# MCU.net
KiCad netlist of a schematic drawn in Altium Designer
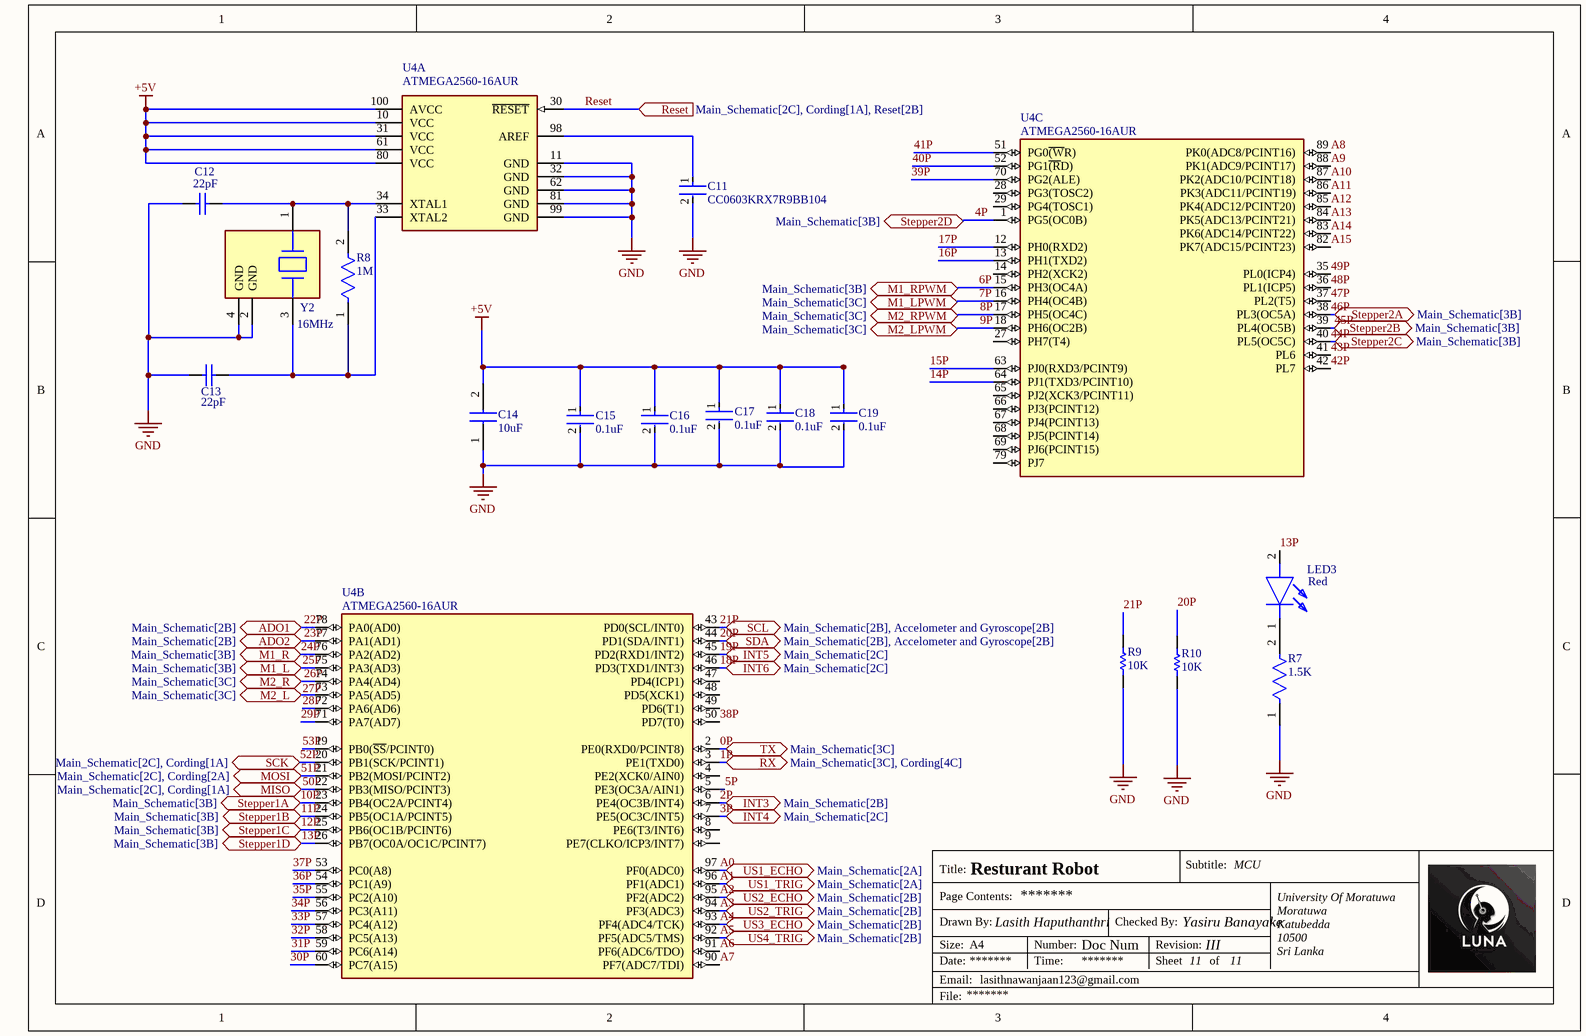
[diagram p0: MCU.SchDoc]

(export (version "E")
  (design (tool "Eeschema 10.0.6"))
  (components
    (comp (ref "C11")
      (value "CC0603KRX7R9BB104")
      (footprint "FP-CC0603-DA-MFG")
      (description "CAP CER 0.1UF 50V X7R 0603")
      (fields (field (name "MANUFACTURER") "YAGEO") (field (name "VOLTAGE") "50 V"))
      (libsource (lib "Altium Content Vault") (part "11868f565c42a9108669ba33697ecf6"))
    )
    (comp (ref "C12")
      (value "22pF")
      (footprint "CAPC1608X90X40LL10T20")
      (libsource (lib "Altium Content Vault") (part "CAP-NP-2"))
    )
    (comp (ref "C13")
      (value "22pF")
      (footprint "CAPC1608X90X40LL10T20")
      (libsource (lib "Altium Content Vault") (part "CAP-NP-2"))
    )
    (comp (ref "C14")
      (value "10uF")
      (footprint "SamacSys:CAPC1608X90N")
      (description "CL10A106KP8NNNC Capacitor")
      (fields
        (field (name "MANUFACTURER_PART_NUMBER") "CL10A106KP8NNNC")
        (field (name "MOUSER PART NUMBER") "187-CL10A106KP8NNNC")
      )
      (libsource (lib "*") (part "CL10A106KP8NNNC"))
    )
    (comp (ref "C15")
      (value "0.1uF")
      (footprint "FP-CC0603-DA-MFG")
      (description "CC0603KRX7R9BB104 CAP CER 0.1UF 50V X7R 0603")
      (fields (field (name "MANUFACTURER") "YAGEO") (field (name "VOLTAGE") "50 V"))
      (libsource (lib "Altium Content Vault") (part "11868f565c42a9108669ba33697ecf6"))
    )
    (comp (ref "C16")
      (value "0.1uF")
      (footprint "FP-CC0603-DA-MFG")
      (description "CC0603KRX7R9BB104 CAP CER 0.1UF 50V X7R 0603")
      (fields (field (name "MANUFACTURER") "YAGEO") (field (name "VOLTAGE") "50 V"))
      (libsource (lib "Altium Content Vault") (part "11868f565c42a9108669ba33697ecf6"))
    )
    (comp (ref "C17")
      (value "0.1uF")
      (footprint "FP-CC0603-DA-MFG")
      (description "CC0603KRX7R9BB104 CAP CER 0.1UF 50V X7R 0603")
      (fields (field (name "MANUFACTURER") "YAGEO") (field (name "VOLTAGE") "50 V"))
      (libsource (lib "Altium Content Vault") (part "11868f565c42a9108669ba33697ecf6"))
    )
    (comp (ref "C18")
      (value "0.1uF")
      (footprint "FP-CC0603-DA-MFG")
      (description "CC0603KRX7R9BB104 CAP CER 0.1UF 50V X7R 0603")
      (fields (field (name "MANUFACTURER") "YAGEO") (field (name "VOLTAGE") "50 V"))
      (libsource (lib "Altium Content Vault") (part "11868f565c42a9108669ba33697ecf6"))
    )
    (comp (ref "C19")
      (value "0.1uF")
      (footprint "FP-CC0603-DA-MFG")
      (description "CC0603KRX7R9BB104 CAP CER 0.1UF 50V X7R 0603")
      (fields (field (name "MANUFACTURER") "YAGEO") (field (name "VOLTAGE") "50 V"))
      (libsource (lib "Altium Content Vault") (part "11868f565c42a9108669ba33697ecf6"))
    )
    (comp (ref "LED3")
      (value "Red")
      (footprint "SamacSys:LEDC1608X55N")
      (description "LED")
      (fields
        (field (name "MANUFACTURER_PART_NUMBER") "LTST-C191KRKT")
        (field (name "MOUSER PART NUMBER") "859-LTST-C191KRKT")
      )
      (libsource (lib "*") (part "LTST-C191KRKT"))
    )
    (comp (ref "R7")
      (value "1.5K")
      (footprint "FP-AF0603-IPC_B")
      (description "AF0603FR-071K5L Anti-Sulfurated Chip Resistors Automotive Grade 1.5kΩ 1% 100ppm/°C 0603")
      (fields (field (name "TOLERANCE") "1%"))
      (libsource (lib "Altium Content Vault") (part "1029c3af85768c4190bb7ad29bc67b5"))
    )
    (comp (ref "R8")
      (value "1M")
      (footprint "FP-AF0603-IPC_B")
      (description "AF0603FR-071K5L Anti-Sulfurated Chip Resistors Automotive Grade 1.5kΩ 1% 100ppm/°C 0603")
      (fields (field (name "TOLERANCE") "1%"))
      (libsource (lib "Altium Content Vault") (part "1029c3af85768c4190bb7ad29bc67b5"))
    )
    (comp (ref "R9")
      (value "10K")
      (footprint "RESC1608X55X25ML10T15")
      (fields (field (name "MANUFACTURER") "Yageo") (field (name "TOLERANCE") "5%"))
      (libsource (lib "Altium Content Vault") (part "RES-2"))
    )
    (comp (ref "R10")
      (value "10K")
      (footprint "RESC1608X55X25ML10T15")
      (fields (field (name "MANUFACTURER") "Yageo") (field (name "TOLERANCE") "5%"))
      (libsource (lib "Altium Content Vault") (part "RES-2"))
    )
    (comp (ref "U4")
      (value "ATMEGA2560-16AUR")
      (footprint "FP-100A-MFG")
      (description "IC MCU 8BIT 256KB FLASH 100TQFP")
      (libsource (lib "Altium Content Vault") (part "7a986b9e50de34ed0d2049ae6a26084"))
    )
    (comp (ref "Y2")
      (value "16MHz")
      (footprint "FP-ABM8G-MFG")
      (fields (field (name "TOLERANCE") "20ppm"))
      (libsource (lib "Altium Content Vault") (part "48e526d86b7f2615d98721063c72f49"))
    )
  )
  (nets
    (net (code "1") (name "+5V") (class "Default")
      (node (ref "C14") (pin "2") (pinfunction "2_2") (pintype "passive"))
      (node (ref "C15") (pin "1") (pinfunction "1_1") (pintype "passive"))
      (node (ref "C16") (pin "1") (pinfunction "1_1") (pintype "passive"))
      (node (ref "C17") (pin "1") (pinfunction "1_1") (pintype "passive"))
      (node (ref "C18") (pin "1") (pinfunction "1_1") (pintype "passive"))
      (node (ref "C19") (pin "1") (pinfunction "1_1") (pintype "passive"))
      (node (ref "U4") (pin "10") (pinfunction "VCC_10") (pintype "power_in"))
      (node (ref "U4") (pin "100") (pinfunction "AVCC_100") (pintype "power_in"))
      (node (ref "U4") (pin "31") (pinfunction "VCC_31") (pintype "power_in"))
      (node (ref "U4") (pin "61") (pinfunction "VCC_61") (pintype "power_in"))
      (node (ref "U4") (pin "80") (pinfunction "VCC_80") (pintype "power_in"))
    )
    (net (code "2") (name "/0P") (class "Default")
      (node (ref "U4") (pin "2") (pinfunction "PE0(RXD0/PCINT8)_2") (pintype "bidirectional"))
    )
    (net (code "3") (name "/1P") (class "Default")
      (node (ref "U4") (pin "3") (pinfunction "PE1(TXD0)_3") (pintype "bidirectional"))
    )
    (net (code "4") (name "/2P") (class "Default")
      (node (ref "U4") (pin "6") (pinfunction "PE4(OC3B/INT4)_6") (pintype "bidirectional"))
    )
    (net (code "5") (name "/3P") (class "Default")
      (node (ref "U4") (pin "7") (pinfunction "PE5(OC3C/INT5)_7") (pintype "bidirectional"))
    )
    (net (code "6") (name "/4P") (class "Default")
      (node (ref "U4") (pin "1") (pinfunction "PG5(OC0B)_1") (pintype "bidirectional"))
    )
    (net (code "7") (name "/5P") (class "Default")
      (node (ref "U4") (pin "5") (pinfunction "PE3(OC3A/AIN1)_5") (pintype "bidirectional"))
    )
    (net (code "8") (name "/6P") (class "Default")
      (node (ref "U4") (pin "15") (pinfunction "PH3(OC4A)_15") (pintype "bidirectional"))
    )
    (net (code "9") (name "/7P") (class "Default")
      (node (ref "U4") (pin "16") (pinfunction "PH4(OC4B)_16") (pintype "bidirectional"))
    )
    (net (code "10") (name "/8P") (class "Default")
      (node (ref "U4") (pin "17") (pinfunction "PH5(OC4C)_17") (pintype "bidirectional"))
    )
    (net (code "11") (name "/9P") (class "Default")
      (node (ref "U4") (pin "18") (pinfunction "PH6(OC2B)_18") (pintype "bidirectional"))
    )
    (net (code "12") (name "/10P") (class "Default")
      (node (ref "U4") (pin "23") (pinfunction "PB4(OC2A/PCINT4)_23") (pintype "bidirectional"))
    )
    (net (code "13") (name "/11P") (class "Default")
      (node (ref "U4") (pin "24") (pinfunction "PB5(OC1A/PCINT5)_24") (pintype "bidirectional"))
    )
    (net (code "14") (name "/12P") (class "Default")
      (node (ref "U4") (pin "25") (pinfunction "PB6(OC1B/PCINT6)_25") (pintype "bidirectional"))
    )
    (net (code "15") (name "/13P") (class "Default")
      (node (ref "LED3") (pin "2") (pinfunction "A_2") (pintype "passive"))
      (node (ref "U4") (pin "26") (pinfunction "PB7(OC0A/OC1C/PCINT7)_26") (pintype "bidirectional"))
    )
    (net (code "16") (name "/14P") (class "Default")
      (node (ref "U4") (pin "64") (pinfunction "PJ1(TXD3/PCINT10)_64") (pintype "bidirectional"))
    )
    (net (code "17") (name "/15P") (class "Default")
      (node (ref "U4") (pin "63") (pinfunction "PJ0(RXD3/PCINT9)_63") (pintype "bidirectional"))
    )
    (net (code "18") (name "/16P") (class "Default")
      (node (ref "U4") (pin "13") (pinfunction "PH1(TXD2)_13") (pintype "bidirectional"))
    )
    (net (code "19") (name "/17P") (class "Default")
      (node (ref "U4") (pin "12") (pinfunction "PH0(RXD2)_12") (pintype "bidirectional"))
    )
    (net (code "20") (name "/18P") (class "Default")
      (node (ref "U4") (pin "46") (pinfunction "PD3(TXD1/INT3)_46") (pintype "bidirectional"))
    )
    (net (code "21") (name "/19P") (class "Default")
      (node (ref "U4") (pin "45") (pinfunction "PD2(RXD1/INT2)_45") (pintype "bidirectional"))
    )
    (net (code "22") (name "/20P") (class "Default")
      (node (ref "R10") (pin "2") (pinfunction "2_2") (pintype "passive"))
      (node (ref "U4") (pin "44") (pinfunction "PD1(SDA/INT1)_44") (pintype "bidirectional"))
    )
    (net (code "23") (name "/21P") (class "Default")
      (node (ref "R9") (pin "2") (pinfunction "2_2") (pintype "passive"))
      (node (ref "U4") (pin "43") (pinfunction "PD0(SCL/INT0)_43") (pintype "bidirectional"))
    )
    (net (code "24") (name "/22P") (class "Default")
      (node (ref "U4") (pin "78") (pinfunction "PA0(AD0)_78") (pintype "bidirectional"))
    )
    (net (code "25") (name "/23P") (class "Default")
      (node (ref "U4") (pin "77") (pinfunction "PA1(AD1)_77") (pintype "bidirectional"))
    )
    (net (code "26") (name "/24P") (class "Default")
      (node (ref "U4") (pin "76") (pinfunction "PA2(AD2)_76") (pintype "bidirectional"))
    )
    (net (code "27") (name "/25P") (class "Default")
      (node (ref "U4") (pin "75") (pinfunction "PA3(AD3)_75") (pintype "bidirectional"))
    )
    (net (code "28") (name "/26P") (class "Default")
      (node (ref "U4") (pin "74") (pinfunction "PA4(AD4)_74") (pintype "bidirectional"))
    )
    (net (code "30") (name "/28P") (class "Default")
      (node (ref "U4") (pin "72") (pinfunction "PA6(AD6)_72") (pintype "bidirectional"))
    )
    (net (code "31") (name "/29P") (class "Default")
      (node (ref "U4") (pin "71") (pinfunction "PA7(AD7)_71") (pintype "bidirectional"))
    )
    (net (code "32") (name "/30P") (class "Default")
      (node (ref "U4") (pin "60") (pinfunction "PC7(A15)_60") (pintype "bidirectional"))
    )
    (net (code "33") (name "/31P") (class "Default")
      (node (ref "U4") (pin "59") (pinfunction "PC6(A14)_59") (pintype "bidirectional"))
    )
    (net (code "34") (name "/32P") (class "Default")
      (node (ref "U4") (pin "58") (pinfunction "PC5(A13)_58") (pintype "bidirectional"))
    )
    (net (code "35") (name "/33P") (class "Default")
      (node (ref "U4") (pin "57") (pinfunction "PC4(A12)_57") (pintype "bidirectional"))
    )
    (net (code "36") (name "/34P") (class "Default")
      (node (ref "U4") (pin "56") (pinfunction "PC3(A11)_56") (pintype "bidirectional"))
    )
    (net (code "37") (name "/35P") (class "Default")
      (node (ref "U4") (pin "55") (pinfunction "PC2(A10)_55") (pintype "bidirectional"))
    )
    (net (code "38") (name "/36P") (class "Default")
      (node (ref "U4") (pin "54") (pinfunction "PC1(A9)_54") (pintype "bidirectional"))
    )
    (net (code "39") (name "/37P") (class "Default")
      (node (ref "U4") (pin "53") (pinfunction "PC0(A8)_53") (pintype "bidirectional"))
    )
    (net (code "40") (name "/38P") (class "Default")
      (node (ref "U4") (pin "50") (pinfunction "PD7(T0)_50") (pintype "bidirectional"))
    )
    (net (code "41") (name "/39P") (class "Default")
      (node (ref "U4") (pin "70") (pinfunction "PG2(ALE)_70") (pintype "bidirectional"))
    )
    (net (code "42") (name "/40P") (class "Default")
      (node (ref "U4") (pin "52") (pinfunction "PG1~{(R}D)_52") (pintype "bidirectional"))
    )
    (net (code "43") (name "/41P") (class "Default")
      (node (ref "U4") (pin "51") (pinfunction "PG0~{(W}R)_51") (pintype "bidirectional"))
    )
    (net (code "44") (name "/42P") (class "Default")
      (node (ref "U4") (pin "42") (pinfunction "PL7_42") (pintype "bidirectional"))
    )
    (net (code "45") (name "/43P") (class "Default")
      (node (ref "U4") (pin "41") (pinfunction "PL6_41") (pintype "bidirectional"))
    )
    (net (code "46") (name "/44P") (class "Default")
      (node (ref "U4") (pin "40") (pinfunction "PL5(OC5C)_40") (pintype "bidirectional"))
    )
    (net (code "47") (name "/45P") (class "Default")
      (node (ref "U4") (pin "39") (pinfunction "PL4(OC5B)_39") (pintype "bidirectional"))
    )
    (net (code "48") (name "/46P") (class "Default")
      (node (ref "U4") (pin "38") (pinfunction "PL3(OC5A)_38") (pintype "bidirectional"))
    )
    (net (code "49") (name "/47P") (class "Default")
      (node (ref "U4") (pin "37") (pinfunction "PL2(T5)_37") (pintype "bidirectional"))
    )
    (net (code "50") (name "/48P") (class "Default")
      (node (ref "U4") (pin "36") (pinfunction "PL1(ICP5)_36") (pintype "bidirectional"))
    )
    (net (code "51") (name "/49P") (class "Default")
      (node (ref "U4") (pin "35") (pinfunction "PL0(ICP4)_35") (pintype "bidirectional"))
    )
    (net (code "52") (name "/50P") (class "Default")
      (node (ref "U4") (pin "22") (pinfunction "PB3(MISO/PCINT3)_22") (pintype "bidirectional"))
    )
    (net (code "54") (name "/52P") (class "Default")
      (node (ref "U4") (pin "20") (pinfunction "PB1(SCK/PCINT1)_20") (pintype "bidirectional"))
    )
    (net (code "55") (name "/53P") (class "Default")
      (node (ref "U4") (pin "19") (pinfunction "PB0(~{SS}/PCINT0)_19") (pintype "bidirectional"))
    )
    (net (code "56") (name "/A0") (class "Default")
      (node (ref "U4") (pin "97") (pinfunction "PF0(ADC0)_97") (pintype "bidirectional"))
    )
    (net (code "57") (name "/A1") (class "Default")
      (node (ref "U4") (pin "96") (pinfunction "PF1(ADC1)_96") (pintype "bidirectional"))
    )
    (net (code "58") (name "/A2") (class "Default")
      (node (ref "U4") (pin "95") (pinfunction "PF2(ADC2)_95") (pintype "bidirectional"))
    )
    (net (code "59") (name "/A3") (class "Default")
      (node (ref "U4") (pin "94") (pinfunction "PF3(ADC3)_94") (pintype "bidirectional"))
    )
    (net (code "60") (name "/A4") (class "Default")
      (node (ref "U4") (pin "93") (pinfunction "PF4(ADC4/TCK)_93") (pintype "bidirectional"))
    )
    (net (code "61") (name "/A5") (class "Default")
      (node (ref "U4") (pin "92") (pinfunction "PF5(ADC5/TMS)_92") (pintype "bidirectional"))
    )
    (net (code "62") (name "/A6") (class "Default")
      (node (ref "U4") (pin "91") (pinfunction "PF6(ADC6/TDO)_91") (pintype "bidirectional"))
    )
    (net (code "63") (name "/A7") (class "Default")
      (node (ref "U4") (pin "90") (pinfunction "PF7(ADC7/TDI)_90") (pintype "bidirectional"))
    )
    (net (code "64") (name "/A8") (class "Default")
      (node (ref "U4") (pin "89") (pinfunction "PK0(ADC8/PCINT16)_89") (pintype "bidirectional"))
    )
    (net (code "65") (name "/A9") (class "Default")
      (node (ref "U4") (pin "88") (pinfunction "PK1(ADC9/PCINT17)_88") (pintype "bidirectional"))
    )
    (net (code "66") (name "/A10") (class "Default")
      (node (ref "U4") (pin "87") (pinfunction "PK2(ADC10/PCINT18)_87") (pintype "bidirectional"))
    )
    (net (code "67") (name "/A11") (class "Default")
      (node (ref "U4") (pin "86") (pinfunction "PK3(ADC11/PCINT19)_86") (pintype "bidirectional"))
    )
    (net (code "68") (name "/A12") (class "Default")
      (node (ref "U4") (pin "85") (pinfunction "PK4(ADC12/PCINT20)_85") (pintype "bidirectional"))
    )
    (net (code "69") (name "/A13") (class "Default")
      (node (ref "U4") (pin "84") (pinfunction "PK5(ADC13/PCINT21)_84") (pintype "bidirectional"))
    )
    (net (code "70") (name "/A14") (class "Default")
      (node (ref "U4") (pin "83") (pinfunction "PK6(ADC14/PCINT22)_83") (pintype "bidirectional"))
    )
    (net (code "71") (name "/A15") (class "Default")
      (node (ref "U4") (pin "82") (pinfunction "PK7(ADC15/PCINT23)_82") (pintype "bidirectional"))
    )
    (net (code "73") (name "/M2_L") (class "Default")
      (node (ref "U4") (pin "73") (pinfunction "PA5(AD5)_73") (pintype "bidirectional"))
    )
    (net (code "75") (name "/MOSI") (class "Default")
      (node (ref "U4") (pin "21") (pinfunction "PB2(MOSI/PCINT2)_21") (pintype "bidirectional"))
    )
    (net (code "76") (name "/Reset") (class "Default")
      (node (ref "U4") (pin "30") (pinfunction "~{RESET}_30") (pintype "input"))
    )
    (net (code "77") (name "GND") (class "Default")
      (node (ref "C11") (pin "2") (pinfunction "2_2") (pintype "passive"))
      (node (ref "C12") (pin "1") (pinfunction "1_1") (pintype "passive"))
      (node (ref "C13") (pin "1") (pinfunction "1_1") (pintype "passive"))
      (node (ref "C14") (pin "1") (pinfunction "1_1") (pintype "passive"))
      (node (ref "C15") (pin "2") (pinfunction "2_2") (pintype "passive"))
      (node (ref "C16") (pin "2") (pinfunction "2_2") (pintype "passive"))
      (node (ref "C17") (pin "2") (pinfunction "2_2") (pintype "passive"))
      (node (ref "C18") (pin "2") (pinfunction "2_2") (pintype "passive"))
      (node (ref "C19") (pin "2") (pinfunction "2_2") (pintype "passive"))
      (node (ref "R10") (pin "1") (pinfunction "1_1") (pintype "passive"))
      (node (ref "R7") (pin "1") (pinfunction "1_1") (pintype "passive"))
      (node (ref "R9") (pin "1") (pinfunction "1_1") (pintype "passive"))
      (node (ref "U4") (pin "11") (pinfunction "GND_11") (pintype "power_in"))
      (node (ref "U4") (pin "32") (pinfunction "GND_32") (pintype "power_in"))
      (node (ref "U4") (pin "62") (pinfunction "GND_62") (pintype "power_in"))
      (node (ref "U4") (pin "81") (pinfunction "GND_81") (pintype "power_in"))
      (node (ref "U4") (pin "99") (pinfunction "GND_99") (pintype "power_in"))
      (node (ref "Y2") (pin "2") (pinfunction "GND_2") (pintype "power_in"))
      (node (ref "Y2") (pin "4") (pinfunction "GND_4") (pintype "power_in"))
    )
    (net (code "78") (name "Net-(LED3-K)") (class "Default")
      (node (ref "LED3") (pin "1") (pinfunction "K_1") (pintype "passive"))
      (node (ref "R7") (pin "2") (pinfunction "2_2") (pintype "passive"))
    )
    (net (code "79") (name "Net-(U4A-AREF)") (class "Default")
      (node (ref "C11") (pin "1") (pinfunction "1_1") (pintype "passive"))
      (node (ref "U4") (pin "98") (pinfunction "AREF_98") (pintype "passive"))
    )
    (net (code "80") (name "Net-(U4A-XTAL1)") (class "Default")
      (node (ref "C12") (pin "2") (pinfunction "2_2") (pintype "passive"))
      (node (ref "R8") (pin "2") (pinfunction "2_2") (pintype "passive"))
      (node (ref "U4") (pin "34") (pinfunction "XTAL1_34") (pintype "passive"))
      (node (ref "Y2") (pin "1") (pinfunction "1_1") (pintype "passive"))
    )
    (net (code "81") (name "Net-(U4A-XTAL2)") (class "Default")
      (node (ref "C13") (pin "2") (pinfunction "2_2") (pintype "passive"))
      (node (ref "R8") (pin "1") (pinfunction "1_1") (pintype "passive"))
      (node (ref "U4") (pin "33") (pinfunction "XTAL2_33") (pintype "passive"))
      (node (ref "Y2") (pin "3") (pinfunction "3_3") (pintype "passive"))
    )
    (net (code "82") (name "unconnected-(U4B-PD4(ICP1)-Pad47)") (class "Default")
      (node (ref "U4") (pin "47") (pinfunction "PD4(ICP1)_47") (pintype "bidirectional"))
    )
    (net (code "83") (name "unconnected-(U4B-PD5(XCK1)-Pad48)") (class "Default")
      (node (ref "U4") (pin "48") (pinfunction "PD5(XCK1)_48") (pintype "bidirectional"))
    )
    (net (code "84") (name "unconnected-(U4B-PD6(T1)-Pad49)") (class "Default")
      (node (ref "U4") (pin "49") (pinfunction "PD6(T1)_49") (pintype "bidirectional"))
    )
    (net (code "85") (name "unconnected-(U4B-PE2(XCK0{slash}AIN0)-Pad4)") (class "Default")
      (node (ref "U4") (pin "4") (pinfunction "PE2(XCK0/AIN0)_4") (pintype "bidirectional"))
    )
    (net (code "86") (name "unconnected-(U4B-PE6(T3{slash}INT6)-Pad8)") (class "Default")
      (node (ref "U4") (pin "8") (pinfunction "PE6(T3/INT6)_8") (pintype "bidirectional"))
    )
    (net (code "87") (name "unconnected-(U4B-PE7(CLKO{slash}ICP3{slash}INT7)-Pad9)") (class "Default")
      (node (ref "U4") (pin "9") (pinfunction "PE7(CLKO/ICP3/INT7)_9") (pintype "bidirectional"))
    )
    (net (code "88") (name "unconnected-(U4C-PG3(TOSC2)-Pad28)") (class "Default")
      (node (ref "U4") (pin "28") (pinfunction "PG3(TOSC2)_28") (pintype "bidirectional"))
    )
    (net (code "89") (name "unconnected-(U4C-PG4(TOSC1)-Pad29)") (class "Default")
      (node (ref "U4") (pin "29") (pinfunction "PG4(TOSC1)_29") (pintype "bidirectional"))
    )
    (net (code "90") (name "unconnected-(U4C-PH2(XCK2)-Pad14)") (class "Default")
      (node (ref "U4") (pin "14") (pinfunction "PH2(XCK2)_14") (pintype "bidirectional"))
    )
    (net (code "91") (name "unconnected-(U4C-PH7(T4)-Pad27)") (class "Default")
      (node (ref "U4") (pin "27") (pinfunction "PH7(T4)_27") (pintype "bidirectional"))
    )
    (net (code "92") (name "unconnected-(U4C-PJ2(XCK3{slash}PCINT11)-Pad65)") (class "Default")
      (node (ref "U4") (pin "65") (pinfunction "PJ2(XCK3/PCINT11)_65") (pintype "bidirectional"))
    )
    (net (code "93") (name "unconnected-(U4C-PJ3(PCINT12)-Pad66)") (class "Default")
      (node (ref "U4") (pin "66") (pinfunction "PJ3(PCINT12)_66") (pintype "bidirectional"))
    )
    (net (code "94") (name "unconnected-(U4C-PJ4(PCINT13)-Pad67)") (class "Default")
      (node (ref "U4") (pin "67") (pinfunction "PJ4(PCINT13)_67") (pintype "bidirectional"))
    )
    (net (code "95") (name "unconnected-(U4C-PJ5(PCINT14)-Pad68)") (class "Default")
      (node (ref "U4") (pin "68") (pinfunction "PJ5(PCINT14)_68") (pintype "bidirectional"))
    )
    (net (code "96") (name "unconnected-(U4C-PJ6(PCINT15)-Pad69)") (class "Default")
      (node (ref "U4") (pin "69") (pinfunction "PJ6(PCINT15)_69") (pintype "bidirectional"))
    )
    (net (code "97") (name "unconnected-(U4C-PJ7-Pad79)") (class "Default")
      (node (ref "U4") (pin "79") (pinfunction "PJ7_79") (pintype "bidirectional"))
    )
  )
)
